# pulsewidth1.net
KiCad netlist of a schematic drawn in Altium Designer
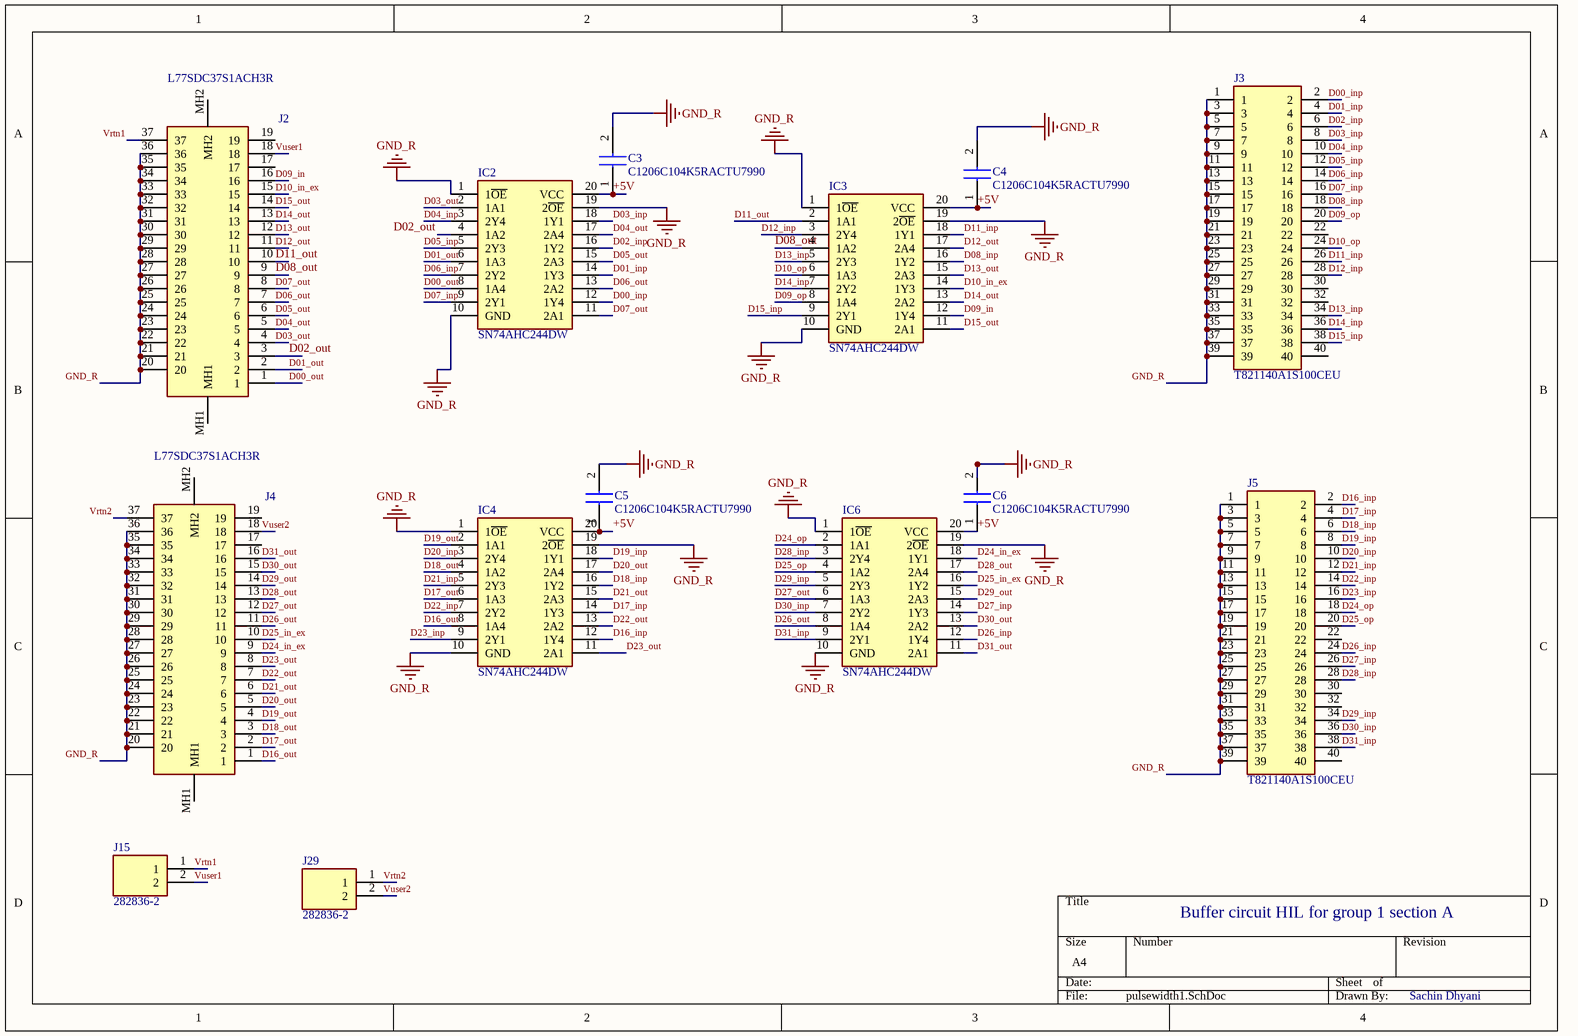
[diagram p0: pulsewidth1.SchDoc]

(export (version "E")
  (design (tool "Eeschema 10.0.6"))
  (components
    (comp (ref "C3")
      (value "C1206C104K5RACTU7990")
      (footprint "SamacSys:CAPC3216X88N")
      (description "Capacitor")
      (libsource (lib "*") (part "C1206C104K5RACTU7990"))
    )
    (comp (ref "C4")
      (value "C1206C104K5RACTU7990")
      (footprint "SamacSys:CAPC3216X88N")
      (description "Capacitor")
      (libsource (lib "*") (part "C1206C104K5RACTU7990"))
    )
    (comp (ref "C5")
      (value "C1206C104K5RACTU7990")
      (footprint "SamacSys:CAPC3216X88N")
      (description "Capacitor")
      (libsource (lib "*") (part "C1206C104K5RACTU7990"))
    )
    (comp (ref "C6")
      (value "C1206C104K5RACTU7990")
      (footprint "SamacSys:CAPC3216X88N")
      (description "Capacitor")
      (libsource (lib "*") (part "C1206C104K5RACTU7990"))
    )
    (comp (ref "IC2")
      (value "SN74AHC244DW")
      (footprint "SamacSys:SOIC127P1030X265-20N")
      (description "Integrated Circuit")
      (fields (field (name "MOUSER PART NUMBER") "595-SN74AHC244DW"))
      (libsource (lib "*") (part "SN74AHC244DW"))
    )
    (comp (ref "IC3")
      (value "SN74AHC244DW")
      (footprint "SamacSys:SOIC127P1030X265-20N")
      (description "Integrated Circuit")
      (fields (field (name "MOUSER PART NUMBER") "595-SN74AHC244DW"))
      (libsource (lib "*") (part "SN74AHC244DW"))
    )
    (comp (ref "IC4")
      (value "SN74AHC244DW")
      (footprint "SamacSys:SOIC127P1030X265-20N")
      (description "Integrated Circuit")
      (fields (field (name "MOUSER PART NUMBER") "595-SN74AHC244DW"))
      (libsource (lib "*") (part "SN74AHC244DW"))
    )
    (comp (ref "IC6")
      (value "SN74AHC244DW")
      (footprint "SamacSys:SOIC127P1030X265-20N")
      (description "Integrated Circuit")
      (fields (field (name "MOUSER PART NUMBER") "595-SN74AHC244DW"))
      (libsource (lib "*") (part "SN74AHC244DW"))
    )
    (comp (ref "J2")
      (value "L77SDC37S1ACH3R")
      (footprint "L77SDC37S1ACH3R")
      (description "Connector")
      (fields (field (name "MOUSER PART NUMBER") "523-L77SDC37S1ACH3R"))
      (libsource (lib "opel_Rt_comps") (part "L77SDC37S1ACH3R"))
    )
    (comp (ref "J3")
      (value "T821140A1S100CEU")
      (footprint "SamacSys:SHDR40W64P254X254_2X20_5842X895X915P")
      (description "Connector")
      (libsource (lib "*") (part "T821140A1S100CEU"))
    )
    (comp (ref "J4")
      (value "L77SDC37S1ACH3R")
      (footprint "L77SDC37S1ACH3R")
      (description "Connector")
      (fields (field (name "MOUSER PART NUMBER") "523-L77SDC37S1ACH3R"))
      (libsource (lib "opel_Rt_comps") (part "L77SDC37S1ACH3R"))
    )
    (comp (ref "J5")
      (value "T821140A1S100CEU")
      (footprint "SamacSys:SHDR40W64P254X254_2X20_5842X895X915P")
      (description "Connector")
      (libsource (lib "*") (part "T821140A1S100CEU"))
    )
    (comp (ref "J15")
      (value "282836-2")
      (footprint "SamacSys:2828362")
      (description "Connector")
      (fields (field (name "MOUSER PART NUMBER") "571-2828362"))
      (libsource (lib "*") (part "282836-2"))
    )
    (comp (ref "J29")
      (value "282836-2")
      (footprint "SamacSys:2828362")
      (description "Connector")
      (fields (field (name "MOUSER PART NUMBER") "571-2828362"))
      (libsource (lib "*") (part "282836-2"))
    )
  )
  (nets
    (net (code "1") (name "/+5V") (class "Default")
      (node (ref "C3") (pin "1") (pinfunction "1_1") (pintype "passive"))
      (node (ref "C4") (pin "1") (pinfunction "1_1") (pintype "passive"))
      (node (ref "C5") (pin "1") (pinfunction "1_1") (pintype "passive"))
      (node (ref "C6") (pin "1") (pinfunction "1_1") (pintype "passive"))
      (node (ref "IC2") (pin "20") (pinfunction "VCC_20") (pintype "passive"))
      (node (ref "IC3") (pin "20") (pinfunction "VCC_20") (pintype "passive"))
      (node (ref "IC4") (pin "20") (pinfunction "VCC_20") (pintype "passive"))
      (node (ref "IC6") (pin "20") (pinfunction "VCC_20") (pintype "passive"))
    )
    (net (code "2") (name "/D00_inp") (class "Default")
      (node (ref "IC2") (pin "12") (pinfunction "1Y4_12") (pintype "passive"))
      (node (ref "J3") (pin "2") (pinfunction "2_2") (pintype "passive"))
    )
    (net (code "3") (name "/D00_out") (class "Default")
      (node (ref "IC2") (pin "8") (pinfunction "1A4_8") (pintype "passive"))
      (node (ref "J2") (pin "1") (pinfunction "1_1") (pintype "passive"))
    )
    (net (code "4") (name "/D01_inp") (class "Default")
      (node (ref "IC2") (pin "14") (pinfunction "1Y3_14") (pintype "passive"))
      (node (ref "J3") (pin "4") (pinfunction "4_4") (pintype "passive"))
    )
    (net (code "5") (name "/D01_out") (class "Default")
      (node (ref "IC2") (pin "6") (pinfunction "1A3_6") (pintype "passive"))
      (node (ref "J2") (pin "2") (pinfunction "2_2") (pintype "passive"))
    )
    (net (code "6") (name "/D02_inp") (class "Default")
      (node (ref "IC2") (pin "16") (pinfunction "1Y2_16") (pintype "passive"))
      (node (ref "J3") (pin "6") (pinfunction "6_6") (pintype "passive"))
    )
    (net (code "7") (name "/D02_out") (class "Default")
      (node (ref "IC2") (pin "4") (pinfunction "1A2_4") (pintype "passive"))
      (node (ref "J2") (pin "3") (pinfunction "3_3") (pintype "passive"))
    )
    (net (code "8") (name "/D03_inp") (class "Default")
      (node (ref "IC2") (pin "18") (pinfunction "1Y1_18") (pintype "passive"))
      (node (ref "J3") (pin "8") (pinfunction "8_8") (pintype "passive"))
    )
    (net (code "9") (name "/D03_out") (class "Default")
      (node (ref "IC2") (pin "2") (pinfunction "1A1_2") (pintype "passive"))
      (node (ref "J2") (pin "4") (pinfunction "4_4") (pintype "passive"))
    )
    (net (code "10") (name "/D04_inp") (class "Default")
      (node (ref "IC2") (pin "3") (pinfunction "2Y4_3") (pintype "passive"))
      (node (ref "J3") (pin "10") (pinfunction "10_10") (pintype "passive"))
    )
    (net (code "11") (name "/D04_out") (class "Default")
      (node (ref "IC2") (pin "17") (pinfunction "2A4_17") (pintype "passive"))
      (node (ref "J2") (pin "5") (pinfunction "5_5") (pintype "passive"))
    )
    (net (code "12") (name "/D05_inp") (class "Default")
      (node (ref "IC2") (pin "5") (pinfunction "2Y3_5") (pintype "passive"))
      (node (ref "J3") (pin "12") (pinfunction "12_12") (pintype "passive"))
    )
    (net (code "13") (name "/D05_out") (class "Default")
      (node (ref "IC2") (pin "15") (pinfunction "2A3_15") (pintype "passive"))
      (node (ref "J2") (pin "6") (pinfunction "6_6") (pintype "passive"))
    )
    (net (code "14") (name "/D06_inp") (class "Default")
      (node (ref "IC2") (pin "7") (pinfunction "2Y2_7") (pintype "passive"))
      (node (ref "J3") (pin "14") (pinfunction "14_14") (pintype "passive"))
    )
    (net (code "15") (name "/D06_out") (class "Default")
      (node (ref "IC2") (pin "13") (pinfunction "2A2_13") (pintype "passive"))
      (node (ref "J2") (pin "7") (pinfunction "7_7") (pintype "passive"))
    )
    (net (code "16") (name "/D07_inp") (class "Default")
      (node (ref "IC2") (pin "9") (pinfunction "2Y1_9") (pintype "passive"))
      (node (ref "J3") (pin "16") (pinfunction "16_16") (pintype "passive"))
    )
    (net (code "17") (name "/D07_out") (class "Default")
      (node (ref "IC2") (pin "11") (pinfunction "2A1_11") (pintype "passive"))
      (node (ref "J2") (pin "8") (pinfunction "8_8") (pintype "passive"))
    )
    (net (code "18") (name "/D08_inp") (class "Default")
      (node (ref "IC3") (pin "16") (pinfunction "1Y2_16") (pintype "passive"))
      (node (ref "J3") (pin "18") (pinfunction "18_18") (pintype "passive"))
    )
    (net (code "19") (name "/D08_out") (class "Default")
      (node (ref "IC3") (pin "4") (pinfunction "1A2_4") (pintype "passive"))
      (node (ref "J2") (pin "9") (pinfunction "9_9") (pintype "passive"))
    )
    (net (code "20") (name "/D09_in") (class "Default")
      (node (ref "IC3") (pin "12") (pinfunction "1Y4_12") (pintype "passive"))
      (node (ref "J2") (pin "16") (pinfunction "16_16") (pintype "passive"))
    )
    (net (code "21") (name "/D09_op") (class "Default")
      (node (ref "IC3") (pin "8") (pinfunction "1A4_8") (pintype "passive"))
      (node (ref "J3") (pin "20") (pinfunction "20_20") (pintype "passive"))
    )
    (net (code "22") (name "/D10_in_ex") (class "Default")
      (node (ref "IC3") (pin "14") (pinfunction "1Y3_14") (pintype "passive"))
      (node (ref "J2") (pin "15") (pinfunction "15_15") (pintype "passive"))
    )
    (net (code "23") (name "/D10_op") (class "Default")
      (node (ref "IC3") (pin "6") (pinfunction "1A3_6") (pintype "passive"))
      (node (ref "J3") (pin "24") (pinfunction "24_24") (pintype "passive"))
    )
    (net (code "24") (name "/D11_inp") (class "Default")
      (node (ref "IC3") (pin "18") (pinfunction "1Y1_18") (pintype "passive"))
      (node (ref "J3") (pin "26") (pinfunction "26_26") (pintype "passive"))
    )
    (net (code "25") (name "/D11_out") (class "Default")
      (node (ref "IC3") (pin "2") (pinfunction "1A1_2") (pintype "passive"))
      (node (ref "J2") (pin "10") (pinfunction "10_10") (pintype "passive"))
    )
    (net (code "26") (name "/D12_inp") (class "Default")
      (node (ref "IC3") (pin "3") (pinfunction "2Y4_3") (pintype "passive"))
      (node (ref "J3") (pin "28") (pinfunction "28_28") (pintype "passive"))
    )
    (net (code "27") (name "/D12_out") (class "Default")
      (node (ref "IC3") (pin "17") (pinfunction "2A4_17") (pintype "passive"))
      (node (ref "J2") (pin "11") (pinfunction "11_11") (pintype "passive"))
    )
    (net (code "28") (name "/D13_inp") (class "Default")
      (node (ref "IC3") (pin "5") (pinfunction "2Y3_5") (pintype "passive"))
      (node (ref "J3") (pin "34") (pinfunction "34_34") (pintype "passive"))
    )
    (net (code "29") (name "/D13_out") (class "Default")
      (node (ref "IC3") (pin "15") (pinfunction "2A3_15") (pintype "passive"))
      (node (ref "J2") (pin "12") (pinfunction "12_12") (pintype "passive"))
    )
    (net (code "30") (name "/D14_inp") (class "Default")
      (node (ref "IC3") (pin "7") (pinfunction "2Y2_7") (pintype "passive"))
      (node (ref "J3") (pin "36") (pinfunction "36_36") (pintype "passive"))
    )
    (net (code "31") (name "/D14_out") (class "Default")
      (node (ref "IC3") (pin "13") (pinfunction "2A2_13") (pintype "passive"))
      (node (ref "J2") (pin "13") (pinfunction "13_13") (pintype "passive"))
    )
    (net (code "32") (name "/D15_inp") (class "Default")
      (node (ref "IC3") (pin "9") (pinfunction "2Y1_9") (pintype "passive"))
      (node (ref "J3") (pin "38") (pinfunction "38_38") (pintype "passive"))
    )
    (net (code "33") (name "/D15_out") (class "Default")
      (node (ref "IC3") (pin "11") (pinfunction "2A1_11") (pintype "passive"))
      (node (ref "J2") (pin "14") (pinfunction "14_14") (pintype "passive"))
    )
    (net (code "34") (name "/D16_inp") (class "Default")
      (node (ref "IC4") (pin "12") (pinfunction "1Y4_12") (pintype "passive"))
      (node (ref "J5") (pin "2") (pinfunction "2_2") (pintype "passive"))
    )
    (net (code "35") (name "/D16_out") (class "Default")
      (node (ref "IC4") (pin "8") (pinfunction "1A4_8") (pintype "passive"))
      (node (ref "J4") (pin "1") (pinfunction "1_1") (pintype "passive"))
    )
    (net (code "36") (name "/D17_inp") (class "Default")
      (node (ref "IC4") (pin "14") (pinfunction "1Y3_14") (pintype "passive"))
      (node (ref "J5") (pin "4") (pinfunction "4_4") (pintype "passive"))
    )
    (net (code "37") (name "/D17_out") (class "Default")
      (node (ref "IC4") (pin "6") (pinfunction "1A3_6") (pintype "passive"))
      (node (ref "J4") (pin "2") (pinfunction "2_2") (pintype "passive"))
    )
    (net (code "38") (name "/D18_inp") (class "Default")
      (node (ref "IC4") (pin "16") (pinfunction "1Y2_16") (pintype "passive"))
      (node (ref "J5") (pin "6") (pinfunction "6_6") (pintype "passive"))
    )
    (net (code "39") (name "/D18_out") (class "Default")
      (node (ref "IC4") (pin "4") (pinfunction "1A2_4") (pintype "passive"))
      (node (ref "J4") (pin "3") (pinfunction "3_3") (pintype "passive"))
    )
    (net (code "40") (name "/D19_inp") (class "Default")
      (node (ref "IC4") (pin "18") (pinfunction "1Y1_18") (pintype "passive"))
      (node (ref "J5") (pin "8") (pinfunction "8_8") (pintype "passive"))
    )
    (net (code "41") (name "/D19_out") (class "Default")
      (node (ref "IC4") (pin "2") (pinfunction "1A1_2") (pintype "passive"))
      (node (ref "J4") (pin "4") (pinfunction "4_4") (pintype "passive"))
    )
    (net (code "42") (name "/D20_inp") (class "Default")
      (node (ref "IC4") (pin "3") (pinfunction "2Y4_3") (pintype "passive"))
      (node (ref "J5") (pin "10") (pinfunction "10_10") (pintype "passive"))
    )
    (net (code "43") (name "/D20_out") (class "Default")
      (node (ref "IC4") (pin "17") (pinfunction "2A4_17") (pintype "passive"))
      (node (ref "J4") (pin "5") (pinfunction "5_5") (pintype "passive"))
    )
    (net (code "44") (name "/D21_inp") (class "Default")
      (node (ref "IC4") (pin "5") (pinfunction "2Y3_5") (pintype "passive"))
      (node (ref "J5") (pin "12") (pinfunction "12_12") (pintype "passive"))
    )
    (net (code "45") (name "/D21_out") (class "Default")
      (node (ref "IC4") (pin "15") (pinfunction "2A3_15") (pintype "passive"))
      (node (ref "J4") (pin "6") (pinfunction "6_6") (pintype "passive"))
    )
    (net (code "46") (name "/D22_inp") (class "Default")
      (node (ref "IC4") (pin "7") (pinfunction "2Y2_7") (pintype "passive"))
      (node (ref "J5") (pin "14") (pinfunction "14_14") (pintype "passive"))
    )
    (net (code "47") (name "/D22_out") (class "Default")
      (node (ref "IC4") (pin "13") (pinfunction "2A2_13") (pintype "passive"))
      (node (ref "J4") (pin "7") (pinfunction "7_7") (pintype "passive"))
    )
    (net (code "48") (name "/D23_inp") (class "Default")
      (node (ref "IC4") (pin "9") (pinfunction "2Y1_9") (pintype "passive"))
      (node (ref "J5") (pin "16") (pinfunction "16_16") (pintype "passive"))
    )
    (net (code "49") (name "/D23_out") (class "Default")
      (node (ref "IC4") (pin "11") (pinfunction "2A1_11") (pintype "passive"))
      (node (ref "J4") (pin "8") (pinfunction "8_8") (pintype "passive"))
    )
    (net (code "50") (name "/D24_in_ex") (class "Default")
      (node (ref "IC6") (pin "18") (pinfunction "1Y1_18") (pintype "passive"))
      (node (ref "J4") (pin "9") (pinfunction "9_9") (pintype "passive"))
    )
    (net (code "51") (name "/D24_op") (class "Default")
      (node (ref "IC6") (pin "2") (pinfunction "1A1_2") (pintype "passive"))
      (node (ref "J5") (pin "18") (pinfunction "18_18") (pintype "passive"))
    )
    (net (code "52") (name "/D25_in_ex") (class "Default")
      (node (ref "IC6") (pin "16") (pinfunction "1Y2_16") (pintype "passive"))
      (node (ref "J4") (pin "10") (pinfunction "10_10") (pintype "passive"))
    )
    (net (code "53") (name "/D25_op") (class "Default")
      (node (ref "IC6") (pin "4") (pinfunction "1A2_4") (pintype "passive"))
      (node (ref "J5") (pin "20") (pinfunction "20_20") (pintype "passive"))
    )
    (net (code "54") (name "/D26_inp") (class "Default")
      (node (ref "IC6") (pin "12") (pinfunction "1Y4_12") (pintype "passive"))
      (node (ref "J5") (pin "24") (pinfunction "24_24") (pintype "passive"))
    )
    (net (code "55") (name "/D26_out") (class "Default")
      (node (ref "IC6") (pin "8") (pinfunction "1A4_8") (pintype "passive"))
      (node (ref "J4") (pin "11") (pinfunction "11_11") (pintype "passive"))
    )
    (net (code "56") (name "/D27_inp") (class "Default")
      (node (ref "IC6") (pin "14") (pinfunction "1Y3_14") (pintype "passive"))
      (node (ref "J5") (pin "26") (pinfunction "26_26") (pintype "passive"))
    )
    (net (code "57") (name "/D27_out") (class "Default")
      (node (ref "IC6") (pin "6") (pinfunction "1A3_6") (pintype "passive"))
      (node (ref "J4") (pin "12") (pinfunction "12_12") (pintype "passive"))
    )
    (net (code "58") (name "/D28_inp") (class "Default")
      (node (ref "IC6") (pin "3") (pinfunction "2Y4_3") (pintype "passive"))
      (node (ref "J5") (pin "28") (pinfunction "28_28") (pintype "passive"))
    )
    (net (code "59") (name "/D28_out") (class "Default")
      (node (ref "IC6") (pin "17") (pinfunction "2A4_17") (pintype "passive"))
      (node (ref "J4") (pin "13") (pinfunction "13_13") (pintype "passive"))
    )
    (net (code "60") (name "/D29_inp") (class "Default")
      (node (ref "IC6") (pin "5") (pinfunction "2Y3_5") (pintype "passive"))
      (node (ref "J5") (pin "34") (pinfunction "34_34") (pintype "passive"))
    )
    (net (code "61") (name "/D29_out") (class "Default")
      (node (ref "IC6") (pin "15") (pinfunction "2A3_15") (pintype "passive"))
      (node (ref "J4") (pin "14") (pinfunction "14_14") (pintype "passive"))
    )
    (net (code "62") (name "/D30_inp") (class "Default")
      (node (ref "IC6") (pin "7") (pinfunction "2Y2_7") (pintype "passive"))
      (node (ref "J5") (pin "36") (pinfunction "36_36") (pintype "passive"))
    )
    (net (code "63") (name "/D30_out") (class "Default")
      (node (ref "IC6") (pin "13") (pinfunction "2A2_13") (pintype "passive"))
      (node (ref "J4") (pin "15") (pinfunction "15_15") (pintype "passive"))
    )
    (net (code "64") (name "/D31_inp") (class "Default")
      (node (ref "IC6") (pin "9") (pinfunction "2Y1_9") (pintype "passive"))
      (node (ref "J5") (pin "38") (pinfunction "38_38") (pintype "passive"))
    )
    (net (code "65") (name "/D31_out") (class "Default")
      (node (ref "IC6") (pin "11") (pinfunction "2A1_11") (pintype "passive"))
      (node (ref "J4") (pin "16") (pinfunction "16_16") (pintype "passive"))
    )
    (net (code "66") (name "/Vrtn1") (class "Default")
      (node (ref "J15") (pin "1") (pinfunction "1_1") (pintype "passive"))
      (node (ref "J2") (pin "37") (pinfunction "37_37") (pintype "passive"))
    )
    (net (code "67") (name "/Vrtn2") (class "Default")
      (node (ref "J29") (pin "1") (pinfunction "1_1") (pintype "passive"))
      (node (ref "J4") (pin "37") (pinfunction "37_37") (pintype "passive"))
    )
    (net (code "68") (name "/Vuser1") (class "Default")
      (node (ref "J15") (pin "2") (pinfunction "2_2") (pintype "passive"))
      (node (ref "J2") (pin "18") (pinfunction "18_18") (pintype "passive"))
    )
    (net (code "69") (name "/Vuser2") (class "Default")
      (node (ref "J29") (pin "2") (pinfunction "2_2") (pintype "passive"))
      (node (ref "J4") (pin "18") (pinfunction "18_18") (pintype "passive"))
    )
    (net (code "70") (name "GND_R") (class "Default")
      (node (ref "C3") (pin "2") (pinfunction "2_2") (pintype "passive"))
      (node (ref "C4") (pin "2") (pinfunction "2_2") (pintype "passive"))
      (node (ref "C5") (pin "2") (pinfunction "2_2") (pintype "passive"))
      (node (ref "C6") (pin "2") (pinfunction "2_2") (pintype "passive"))
      (node (ref "IC2") (pin "1") (pinfunction "1~{OE}_1") (pintype "passive"))
      (node (ref "IC2") (pin "10") (pinfunction "GND_10") (pintype "passive"))
      (node (ref "IC2") (pin "19") (pinfunction "2~{OE}_19") (pintype "passive"))
      (node (ref "IC3") (pin "1") (pinfunction "1~{OE}_1") (pintype "passive"))
      (node (ref "IC3") (pin "10") (pinfunction "GND_10") (pintype "passive"))
      (node (ref "IC3") (pin "19") (pinfunction "2~{OE}_19") (pintype "passive"))
      (node (ref "IC4") (pin "1") (pinfunction "1~{OE}_1") (pintype "passive"))
      (node (ref "IC4") (pin "10") (pinfunction "GND_10") (pintype "passive"))
      (node (ref "IC4") (pin "19") (pinfunction "2~{OE}_19") (pintype "passive"))
      (node (ref "IC6") (pin "1") (pinfunction "1~{OE}_1") (pintype "passive"))
      (node (ref "IC6") (pin "10") (pinfunction "GND_10") (pintype "passive"))
      (node (ref "IC6") (pin "19") (pinfunction "2~{OE}_19") (pintype "passive"))
      (node (ref "J2") (pin "20") (pinfunction "20_20") (pintype "passive"))
      (node (ref "J2") (pin "21") (pinfunction "21_21") (pintype "passive"))
      (node (ref "J2") (pin "22") (pinfunction "22_22") (pintype "passive"))
      (node (ref "J2") (pin "23") (pinfunction "23_23") (pintype "passive"))
      (node (ref "J2") (pin "24") (pinfunction "24_24") (pintype "passive"))
      (node (ref "J2") (pin "25") (pinfunction "25_25") (pintype "passive"))
      (node (ref "J2") (pin "26") (pinfunction "26_26") (pintype "passive"))
      (node (ref "J2") (pin "27") (pinfunction "27_27") (pintype "passive"))
      (node (ref "J2") (pin "28") (pinfunction "28_28") (pintype "passive"))
      (node (ref "J2") (pin "29") (pinfunction "29_29") (pintype "passive"))
      (node (ref "J2") (pin "30") (pinfunction "30_30") (pintype "passive"))
      (node (ref "J2") (pin "31") (pinfunction "31_31") (pintype "passive"))
      (node (ref "J2") (pin "32") (pinfunction "32_32") (pintype "passive"))
      (node (ref "J2") (pin "33") (pinfunction "33_33") (pintype "passive"))
      (node (ref "J2") (pin "34") (pinfunction "34_34") (pintype "passive"))
      (node (ref "J2") (pin "35") (pinfunction "35_35") (pintype "passive"))
      (node (ref "J2") (pin "36") (pinfunction "36_36") (pintype "passive"))
      (node (ref "J3") (pin "1") (pinfunction "1_1") (pintype "passive"))
      (node (ref "J3") (pin "11") (pinfunction "11_11") (pintype "passive"))
      (node (ref "J3") (pin "13") (pinfunction "13_13") (pintype "passive"))
      (node (ref "J3") (pin "15") (pinfunction "15_15") (pintype "passive"))
      (node (ref "J3") (pin "17") (pinfunction "17_17") (pintype "passive"))
      (node (ref "J3") (pin "19") (pinfunction "19_19") (pintype "passive"))
      (node (ref "J3") (pin "21") (pinfunction "21_21") (pintype "passive"))
      (node (ref "J3") (pin "23") (pinfunction "23_23") (pintype "passive"))
      (node (ref "J3") (pin "25") (pinfunction "25_25") (pintype "passive"))
      (node (ref "J3") (pin "27") (pinfunction "27_27") (pintype "passive"))
      (node (ref "J3") (pin "29") (pinfunction "29_29") (pintype "passive"))
      (node (ref "J3") (pin "3") (pinfunction "3_3") (pintype "passive"))
      (node (ref "J3") (pin "31") (pinfunction "31_31") (pintype "passive"))
      (node (ref "J3") (pin "33") (pinfunction "33_33") (pintype "passive"))
      (node (ref "J3") (pin "35") (pinfunction "35_35") (pintype "passive"))
      (node (ref "J3") (pin "37") (pinfunction "37_37") (pintype "passive"))
      (node (ref "J3") (pin "39") (pinfunction "39_39") (pintype "passive"))
      (node (ref "J3") (pin "5") (pinfunction "5_5") (pintype "passive"))
      (node (ref "J3") (pin "7") (pinfunction "7_7") (pintype "passive"))
      (node (ref "J3") (pin "9") (pinfunction "9_9") (pintype "passive"))
      (node (ref "J4") (pin "20") (pinfunction "20_20") (pintype "passive"))
      (node (ref "J4") (pin "21") (pinfunction "21_21") (pintype "passive"))
      (node (ref "J4") (pin "22") (pinfunction "22_22") (pintype "passive"))
      (node (ref "J4") (pin "23") (pinfunction "23_23") (pintype "passive"))
      (node (ref "J4") (pin "24") (pinfunction "24_24") (pintype "passive"))
      (node (ref "J4") (pin "25") (pinfunction "25_25") (pintype "passive"))
      (node (ref "J4") (pin "26") (pinfunction "26_26") (pintype "passive"))
      (node (ref "J4") (pin "27") (pinfunction "27_27") (pintype "passive"))
      (node (ref "J4") (pin "28") (pinfunction "28_28") (pintype "passive"))
      (node (ref "J4") (pin "29") (pinfunction "29_29") (pintype "passive"))
      (node (ref "J4") (pin "30") (pinfunction "30_30") (pintype "passive"))
      (node (ref "J4") (pin "31") (pinfunction "31_31") (pintype "passive"))
      (node (ref "J4") (pin "32") (pinfunction "32_32") (pintype "passive"))
      (node (ref "J4") (pin "33") (pinfunction "33_33") (pintype "passive"))
      (node (ref "J4") (pin "34") (pinfunction "34_34") (pintype "passive"))
      (node (ref "J4") (pin "35") (pinfunction "35_35") (pintype "passive"))
      (node (ref "J4") (pin "36") (pinfunction "36_36") (pintype "passive"))
      (node (ref "J5") (pin "1") (pinfunction "1_1") (pintype "passive"))
      (node (ref "J5") (pin "11") (pinfunction "11_11") (pintype "passive"))
      (node (ref "J5") (pin "13") (pinfunction "13_13") (pintype "passive"))
      (node (ref "J5") (pin "15") (pinfunction "15_15") (pintype "passive"))
      (node (ref "J5") (pin "17") (pinfunction "17_17") (pintype "passive"))
      (node (ref "J5") (pin "19") (pinfunction "19_19") (pintype "passive"))
      (node (ref "J5") (pin "21") (pinfunction "21_21") (pintype "passive"))
      (node (ref "J5") (pin "23") (pinfunction "23_23") (pintype "passive"))
      (node (ref "J5") (pin "25") (pinfunction "25_25") (pintype "passive"))
      (node (ref "J5") (pin "27") (pinfunction "27_27") (pintype "passive"))
      (node (ref "J5") (pin "29") (pinfunction "29_29") (pintype "passive"))
      (node (ref "J5") (pin "3") (pinfunction "3_3") (pintype "passive"))
      (node (ref "J5") (pin "31") (pinfunction "31_31") (pintype "passive"))
      (node (ref "J5") (pin "33") (pinfunction "33_33") (pintype "passive"))
      (node (ref "J5") (pin "35") (pinfunction "35_35") (pintype "passive"))
      (node (ref "J5") (pin "37") (pinfunction "37_37") (pintype "passive"))
      (node (ref "J5") (pin "39") (pinfunction "39_39") (pintype "passive"))
      (node (ref "J5") (pin "5") (pinfunction "5_5") (pintype "passive"))
      (node (ref "J5") (pin "7") (pinfunction "7_7") (pintype "passive"))
      (node (ref "J5") (pin "9") (pinfunction "9_9") (pintype "passive"))
    )
    (net (code "71") (name "unconnected-(J2-Pad17)") (class "Default")
      (node (ref "J2") (pin "17") (pinfunction "17_17") (pintype "passive"))
    )
    (net (code "72") (name "unconnected-(J2-Pad19)") (class "Default")
      (node (ref "J2") (pin "19") (pinfunction "19_19") (pintype "passive"))
    )
    (net (code "73") (name "unconnected-(J2-PadMH1)") (class "Default")
      (node (ref "J2") (pin "MH1") (pinfunction "MH1_MH1") (pintype "passive"))
    )
    (net (code "74") (name "unconnected-(J2-PadMH2)") (class "Default")
      (node (ref "J2") (pin "MH2") (pinfunction "MH2_MH2") (pintype "passive"))
    )
    (net (code "75") (name "unconnected-(J3-Pad22)") (class "Default")
      (node (ref "J3") (pin "22") (pinfunction "22_22") (pintype "passive"))
    )
    (net (code "76") (name "unconnected-(J3-Pad30)") (class "Default")
      (node (ref "J3") (pin "30") (pinfunction "30_30") (pintype "passive"))
    )
    (net (code "77") (name "unconnected-(J3-Pad32)") (class "Default")
      (node (ref "J3") (pin "32") (pinfunction "32_32") (pintype "passive"))
    )
    (net (code "78") (name "unconnected-(J3-Pad40)") (class "Default")
      (node (ref "J3") (pin "40") (pinfunction "40_40") (pintype "passive"))
    )
    (net (code "79") (name "unconnected-(J4-Pad17)") (class "Default")
      (node (ref "J4") (pin "17") (pinfunction "17_17") (pintype "passive"))
    )
    (net (code "80") (name "unconnected-(J4-Pad19)") (class "Default")
      (node (ref "J4") (pin "19") (pinfunction "19_19") (pintype "passive"))
    )
    (net (code "81") (name "unconnected-(J4-PadMH1)") (class "Default")
      (node (ref "J4") (pin "MH1") (pinfunction "MH1_MH1") (pintype "passive"))
    )
    (net (code "82") (name "unconnected-(J4-PadMH2)") (class "Default")
      (node (ref "J4") (pin "MH2") (pinfunction "MH2_MH2") (pintype "passive"))
    )
    (net (code "83") (name "unconnected-(J5-Pad22)") (class "Default")
      (node (ref "J5") (pin "22") (pinfunction "22_22") (pintype "passive"))
    )
    (net (code "84") (name "unconnected-(J5-Pad30)") (class "Default")
      (node (ref "J5") (pin "30") (pinfunction "30_30") (pintype "passive"))
    )
    (net (code "85") (name "unconnected-(J5-Pad32)") (class "Default")
      (node (ref "J5") (pin "32") (pinfunction "32_32") (pintype "passive"))
    )
    (net (code "86") (name "unconnected-(J5-Pad40)") (class "Default")
      (node (ref "J5") (pin "40") (pinfunction "40_40") (pintype "passive"))
    )
  )
)
